# MIOS-Emphase.net
KiCad netlist of a schematic drawn in Altium Designer
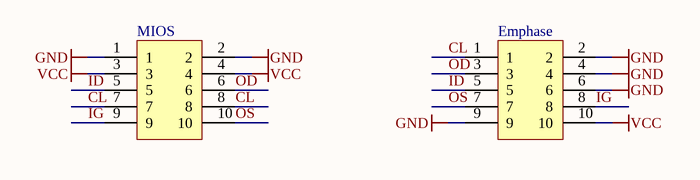
[diagram p0: MIOS-Emphase.SchDoc]

(export (version "E")
  (design (tool "Eeschema 10.0.6"))
  (components
    (comp (ref "Emphase")
      (value "10 pol Header")
      (footprint "10 pol Header")
      (fields (field (name "PUBLISHER") "NONLINEAR LABS"))
      (libsource (lib "10polHeader") (part "10 pol Header"))
    )
    (comp (ref "MIOS")
      (value "10 pol Header")
      (footprint "10 pol Header")
      (fields (field (name "PUBLISHER") "NONLINEAR LABS"))
      (libsource (lib "10polHeader") (part "10 pol Header"))
    )
  )
  (nets
    (net (code "1") (name "/CL") (class "Default")
      (node (ref "Emphase") (pin "1") (pinfunction "1_1") (pintype "passive"))
      (node (ref "MIOS") (pin "7") (pinfunction "7_7") (pintype "passive"))
      (node (ref "MIOS") (pin "8") (pinfunction "8_8") (pintype "passive"))
    )
    (net (code "2") (name "/ID") (class "Default")
      (node (ref "Emphase") (pin "5") (pinfunction "5_5") (pintype "passive"))
      (node (ref "MIOS") (pin "5") (pinfunction "5_5") (pintype "passive"))
    )
    (net (code "3") (name "/IG") (class "Default")
      (node (ref "Emphase") (pin "8") (pinfunction "8_8") (pintype "passive"))
      (node (ref "MIOS") (pin "9") (pinfunction "9_9") (pintype "passive"))
    )
    (net (code "4") (name "/OD") (class "Default")
      (node (ref "Emphase") (pin "3") (pinfunction "3_3") (pintype "passive"))
      (node (ref "MIOS") (pin "6") (pinfunction "6_6") (pintype "passive"))
    )
    (net (code "5") (name "/OS") (class "Default")
      (node (ref "Emphase") (pin "7") (pinfunction "7_7") (pintype "passive"))
      (node (ref "MIOS") (pin "10") (pinfunction "10_10") (pintype "passive"))
    )
    (net (code "6") (name "GND") (class "Default")
      (node (ref "Emphase") (pin "2") (pinfunction "2_2") (pintype "passive"))
      (node (ref "Emphase") (pin "4") (pinfunction "4_4") (pintype "passive"))
      (node (ref "Emphase") (pin "6") (pinfunction "6_6") (pintype "passive"))
      (node (ref "Emphase") (pin "9") (pinfunction "9_9") (pintype "passive"))
      (node (ref "MIOS") (pin "1") (pinfunction "1_1") (pintype "passive"))
      (node (ref "MIOS") (pin "2") (pinfunction "2_2") (pintype "passive"))
    )
    (net (code "7") (name "VCC") (class "Default")
      (node (ref "Emphase") (pin "10") (pinfunction "10_10") (pintype "passive"))
      (node (ref "MIOS") (pin "3") (pinfunction "3_3") (pintype "passive"))
      (node (ref "MIOS") (pin "4") (pinfunction "4_4") (pintype "passive"))
    )
  )
)
